# anti-trip-earth-leakage-detector.net
KiCad netlist of a schematic drawn in EAGLE
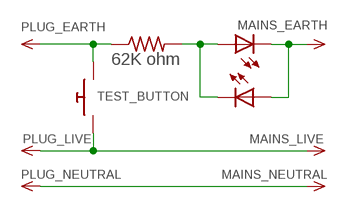
[diagram p0: schematic, sheet 1]

(export (version "E")
  (design (tool "Eeschema 10.0.6"))
  (components
    (comp (ref "LED1")
      (value "LED5MM")
      (footprint "eagle-import:LED5MM")
      (libsource (lib "eagle-import") (part "LED5MM"))
    )
    (comp (ref "LED2")
      (value "LED5MM")
      (footprint "eagle-import:LED5MM")
      (libsource (lib "eagle-import") (part "LED5MM"))
    )
    (comp (ref "R1")
      (value "62K ohm")
      (footprint "eagle-import:0207_10")
      (libsource (lib "eagle-import") (part "R-US_0207/10"))
    )
    (comp (ref "TEST_BUTTON")
      (value "SWITCH_PUSHBUTTONC&K_KSS")
      (footprint "eagle-import:BTN_CK_KSS")
      (libsource (lib "eagle-import") (part "SWITCH_PUSHBUTTONC&K_KSS"))
    )
  )
  (nets
    (net (code "1") (name "Net-(LED2-C)") (class "Default")
      (node (ref "LED1") (pin "A") (pinfunction "A_A") (pintype "passive"))
      (node (ref "LED2") (pin "K") (pinfunction "C_K") (pintype "passive"))
      (node (ref "R1") (pin "2") (pinfunction "2_2") (pintype "passive"))
    )
    (net (code "2") (name "SUPPLY") (class "Default")
      (node (ref "LED1") (pin "K") (pinfunction "C_K") (pintype "passive"))
      (node (ref "LED2") (pin "A") (pinfunction "A_A") (pintype "passive"))
      (node (ref "R1") (pin "1") (pinfunction "1_1") (pintype "passive"))
      (node (ref "TEST_BUTTON") (pin "P$1") (pinfunction "P$1_P$1") (pintype "passive"))
      (node (ref "TEST_BUTTON") (pin "P$2") (pinfunction "P$2_P$2") (pintype "passive"))
    )
  )
)
